# Beechat_Crank_v1_2_B.net
KiCad netlist of a schematic drawn in EAGLE
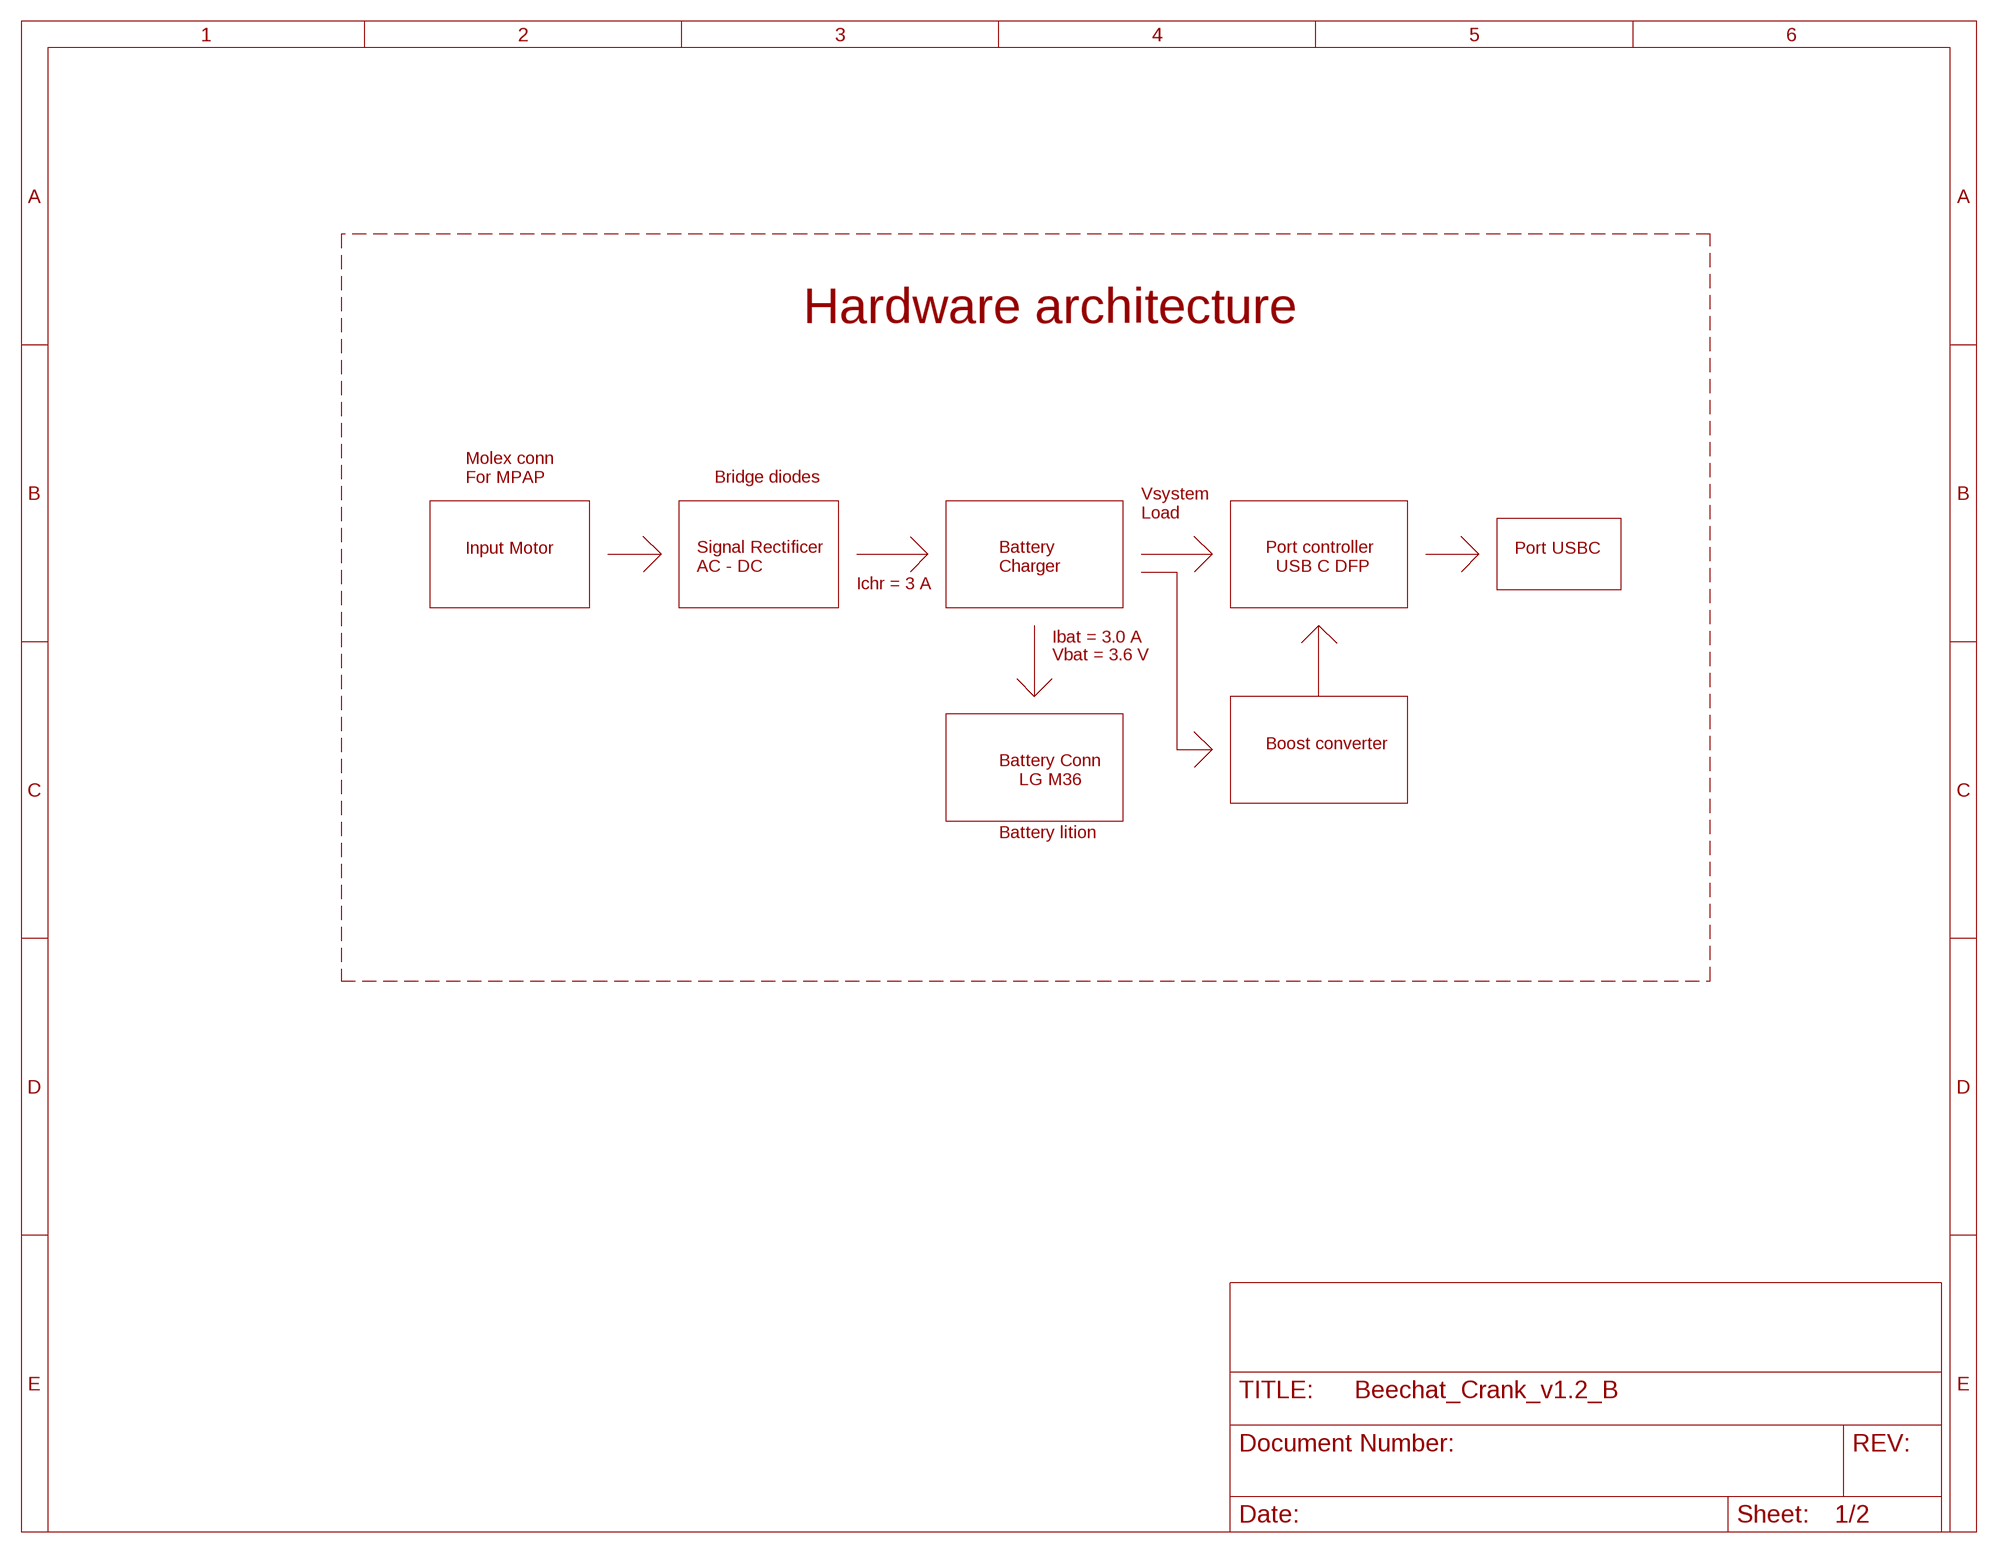
[diagram p0: schematic, sheet 1]
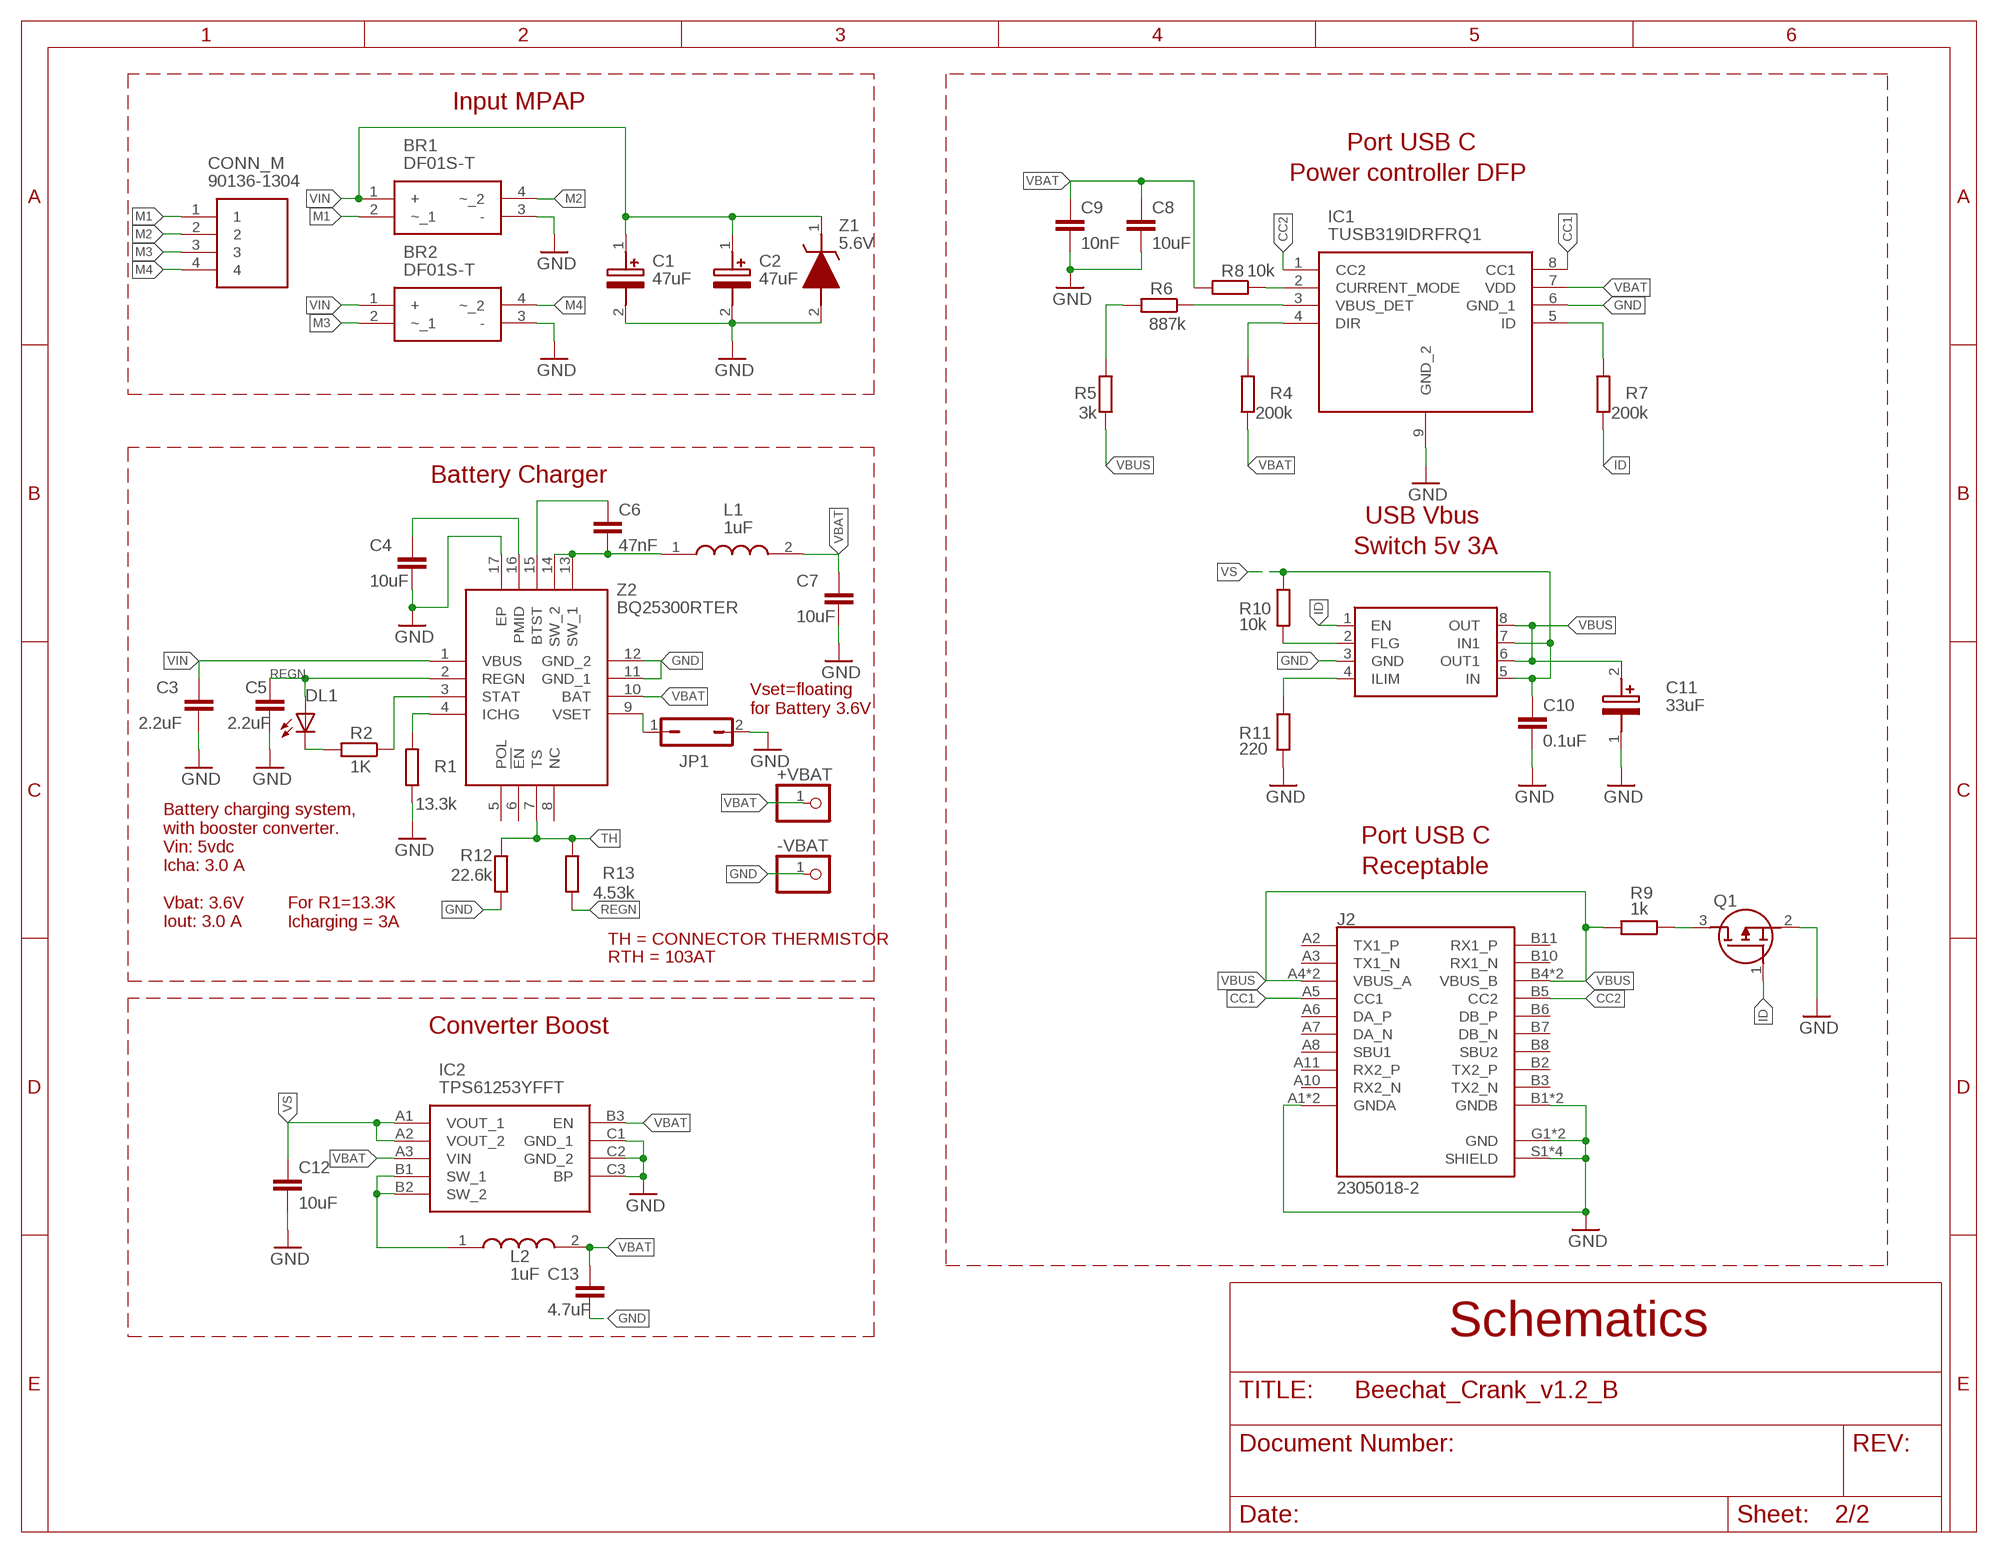
[diagram p1: schematic, sheet 2]

(export (version "E")
  (design (tool "Eeschema 10.0.6"))
  (components
    (comp (ref "+VBAT")
      (value "PINHD-1X1")
      (footprint "eagle-import:1X01")
      (libsource (lib "eagle-import") (part "PINHD-1X1"))
    )
    (comp (ref "-VBAT")
      (value "PINHD-1X1")
      (footprint "eagle-import:1X01")
      (libsource (lib "eagle-import") (part "PINHD-1X1"))
    )
    (comp (ref "BR1")
      (value "DF01S-T")
      (footprint "eagle-import:SOP510P1040X293-4N")
      (fields (field (name "MOUSER_PART_NUMBER") "621-DF01ST"))
      (libsource (lib "eagle-import") (part "DF01S-T"))
    )
    (comp (ref "BR2")
      (value "DF01S-T")
      (footprint "eagle-import:SOP510P1040X293-4N")
      (fields (field (name "MOUSER_PART_NUMBER") "621-DF01ST"))
      (libsource (lib "eagle-import") (part "DF01S-T"))
    )
    (comp (ref "C1")
      (value "47uF")
      (footprint "eagle-import:CAPAE660X800N")
      (fields
        (field (name "MANUFACTURER_PART_NUMBER") "EEE-HDV470XAP")
        (field (name "MOUSER_PART_NUMBER") "667-EEE-HDV470XAP")
      )
      (libsource (lib "eagle-import") (part "EEE-HDV470XAP"))
    )
    (comp (ref "C2")
      (value "47uF")
      (footprint "eagle-import:CAPAE660X800N")
      (fields
        (field (name "MANUFACTURER_PART_NUMBER") "EEE-HDV470XAP")
        (field (name "MOUSER_PART_NUMBER") "667-EEE-HDV470XAP")
      )
      (libsource (lib "eagle-import") (part "EEE-HDV470XAP"))
    )
    (comp (ref "C3")
      (value "2.2uF")
      (footprint "eagle-import:C0603")
      (libsource (lib "eagle-import") (part "C-EUC0603"))
    )
    (comp (ref "C4")
      (value "10uF")
      (footprint "eagle-import:C1210")
      (libsource (lib "eagle-import") (part "C-EUC1210"))
    )
    (comp (ref "C5")
      (value "2.2uF")
      (footprint "eagle-import:C0603")
      (libsource (lib "eagle-import") (part "C-EUC0603"))
    )
    (comp (ref "C6")
      (value "47nF")
      (footprint "eagle-import:C0603")
      (libsource (lib "eagle-import") (part "C-EUC0603"))
    )
    (comp (ref "C7")
      (value "10uF")
      (footprint "eagle-import:C1210")
      (libsource (lib "eagle-import") (part "C-EUC1210"))
    )
    (comp (ref "C8")
      (value "10uF")
      (footprint "eagle-import:C0603")
      (libsource (lib "eagle-import") (part "C-EUC0603"))
    )
    (comp (ref "C9")
      (value "10nF")
      (footprint "eagle-import:C0603")
      (libsource (lib "eagle-import") (part "C-EUC0603"))
    )
    (comp (ref "C10")
      (value "0.1uF")
      (footprint "eagle-import:C0603")
      (libsource (lib "eagle-import") (part "C-EUC0603"))
    )
    (comp (ref "C11")
      (value "33uF")
      (footprint "eagle-import:CAPAE660X550N")
      (fields
        (field (name "MANUFACTURER_PART_NUMBER") "865230343003")
        (field (name "MOUSER_PART_NUMBER") "710-865230343003")
      )
      (libsource (lib "eagle-import") (part "865230343003"))
    )
    (comp (ref "C12")
      (value "10uF")
      (footprint "eagle-import:C0603")
      (libsource (lib "eagle-import") (part "C-EUC0603"))
    )
    (comp (ref "C13")
      (value "4.7uF")
      (footprint "eagle-import:C0603")
      (libsource (lib "eagle-import") (part "C-EUC0603"))
    )
    (comp (ref "CONN_M")
      (value "90136-1304")
      (footprint "eagle-import:SHDR4W65P0X254_1X4_1351X721X11")
      (fields (field (name "MOUSER_PART_NUMBER") "538-90136-1304"))
      (libsource (lib "eagle-import") (part "90136-1304"))
    )
    (comp (ref "DL1")
      (value "LED_BLUE")
      (footprint "eagle-import:CHIP-LED0603")
      (libsource (lib "eagle-import") (part "LEDSMD0603"))
    )
    (comp (ref "IC1")
      (value "TUSB319IDRFRQ1")
      (footprint "eagle-import:SON50P200X200X80-9N")
      (fields (field (name "MOUSER_PART_NUMBER") "595-TUSB319IDRFRQ1"))
      (libsource (lib "eagle-import") (part "TUSB319IDRFRQ1"))
    )
    (comp (ref "IC2")
      (value "TPS61253YFFT")
      (footprint "eagle-import:BGA9C40P3X3_121X131X62")
      (fields (field (name "MOUSER_PART_NUMBER") "595-TPS61253YFFT"))
      (libsource (lib "eagle-import") (part "TPS61253YFFT"))
    )
    (comp (ref "J2")
      (value "2305018-2")
      (footprint "eagle-import:TE_2305018-2")
      (fields (field (name "MF") "TE Connectivity"))
      (libsource (lib "eagle-import") (part "2305018-2"))
    )
    (comp (ref "JP1")
      (value "JP1Q")
      (footprint "eagle-import:JP1")
      (libsource (lib "eagle-import") (part "JP1Q"))
    )
    (comp (ref "L1")
      (value "1uF")
      (footprint "eagle-import:LQH5BPB100MT0L")
      (fields
        (field (name "MANUFACTURER_PART_NUMBER") "LQH5BPB1R0NT0L")
        (field (name "MOUSER_PART_NUMBER") "81-LQH5BPB1R0NT0L")
      )
      (libsource (lib "eagle-import") (part "LQH5BPB1R0NT0L"))
    )
    (comp (ref "L2")
      (value "1uF")
      (footprint "eagle-import:LQH5BPB100MT0L")
      (fields
        (field (name "MANUFACTURER_PART_NUMBER") "LQH5BPB1R0NT0L")
        (field (name "MOUSER_PART_NUMBER") "81-LQH5BPB1R0NT0L")
      )
      (libsource (lib "eagle-import") (part "LQH5BPB1R0NT0L"))
    )
    (comp (ref "Q1")
      (value "SI2337DS-T1-BE3")
      (footprint "eagle-import:SOT95P237X112-3N")
      (fields (field (name "MOUSER_PART_NUMBER") "78-SI2337DS-T1-BE3"))
      (libsource (lib "eagle-import") (part "SI2337DS-T1-BE3"))
    )
    (comp (ref "R1")
      (value "13.3k")
      (footprint "eagle-import:R0603")
      (libsource (lib "eagle-import") (part "R_0603"))
    )
    (comp (ref "R2")
      (value "1K")
      (footprint "eagle-import:R0603")
      (libsource (lib "eagle-import") (part "R_0603"))
    )
    (comp (ref "R4")
      (value "200k")
      (footprint "eagle-import:R0603")
      (libsource (lib "eagle-import") (part "R_0603"))
    )
    (comp (ref "R5")
      (value "3k")
      (footprint "eagle-import:R0603")
      (libsource (lib "eagle-import") (part "R_0603"))
    )
    (comp (ref "R6")
      (value "887k")
      (footprint "eagle-import:R0603")
      (libsource (lib "eagle-import") (part "R_0603"))
    )
    (comp (ref "R7")
      (value "200k")
      (footprint "eagle-import:R0603")
      (libsource (lib "eagle-import") (part "R_0603"))
    )
    (comp (ref "R8")
      (value "10k")
      (footprint "eagle-import:R0603")
      (libsource (lib "eagle-import") (part "R_0603"))
    )
    (comp (ref "R9")
      (value "1k")
      (footprint "eagle-import:R0603")
      (libsource (lib "eagle-import") (part "R_0603"))
    )
    (comp (ref "R10")
      (value "10k")
      (footprint "eagle-import:R0603")
      (libsource (lib "eagle-import") (part "R_0603"))
    )
    (comp (ref "R11")
      (value "220")
      (footprint "eagle-import:R0603")
      (libsource (lib "eagle-import") (part "R_0603"))
    )
    (comp (ref "R12")
      (value "22.6k")
      (footprint "eagle-import:R0603")
      (libsource (lib "eagle-import") (part "R_0603"))
    )
    (comp (ref "R13")
      (value "4.53k")
      (footprint "eagle-import:R0603")
      (libsource (lib "eagle-import") (part "R_0603"))
    )
    (comp (ref "U$1")
      (value "MIC2545")
      (footprint "eagle-import:SOIC127P599X173-8N")
      (libsource (lib "eagle-import") (part "MIC2545"))
    )
    (comp (ref "Z1")
      (value "5.6V")
      (footprint "eagle-import:SOD3716X135N")
      (fields
        (field (name "MANUFACTURER_PART_NUMBER") "MMSZ5V6T3G")
        (field (name "MOUSER_PART_NUMBER") "863-MMSZ5V6T3G")
      )
      (libsource (lib "eagle-import") (part "MMSZ5V6T3G"))
    )
    (comp (ref "Z2")
      (value "BQ25300RTER")
      (footprint "eagle-import:QFN50P300X300X80-17N")
      (fields (field (name "MOUSER_PART_NUMBER") "595-BQ25300RTER"))
      (libsource (lib "eagle-import") (part "BQ25300RTER"))
    )
  )
  (nets
    (net (code "1") (name "CC1") (class "Default")
      (node (ref "IC1") (pin "8") (pinfunction "CC1_8") (pintype "bidirectional"))
      (node (ref "J2") (pin "A5") (pinfunction "CC1_A5") (pintype "passive"))
    )
    (net (code "2") (name "CC2") (class "Default")
      (node (ref "IC1") (pin "1") (pinfunction "CC2_1") (pintype "bidirectional"))
      (node (ref "J2") (pin "B5") (pinfunction "CC2_B5") (pintype "passive"))
    )
    (net (code "3") (name "GND") (class "Default")
      (node (ref "-VBAT") (pin "1") (pinfunction "1_1") (pintype "passive"))
      (node (ref "BR1") (pin "3") (pinfunction "-_3") (pintype "bidirectional"))
      (node (ref "BR2") (pin "3") (pinfunction "-_3") (pintype "bidirectional"))
      (node (ref "C1") (pin "2") (pinfunction "-_2") (pintype "bidirectional"))
      (node (ref "C10") (pin "2") (pinfunction "2_2") (pintype "passive"))
      (node (ref "C11") (pin "1") (pinfunction "-_1") (pintype "bidirectional"))
      (node (ref "C12") (pin "2") (pinfunction "2_2") (pintype "passive"))
      (node (ref "C13") (pin "2") (pinfunction "2_2") (pintype "passive"))
      (node (ref "C2") (pin "2") (pinfunction "-_2") (pintype "bidirectional"))
      (node (ref "C3") (pin "2") (pinfunction "2_2") (pintype "passive"))
      (node (ref "C4") (pin "2") (pinfunction "2_2") (pintype "passive"))
      (node (ref "C5") (pin "2") (pinfunction "2_2") (pintype "passive"))
      (node (ref "C7") (pin "2") (pinfunction "2_2") (pintype "passive"))
      (node (ref "C8") (pin "2") (pinfunction "2_2") (pintype "passive"))
      (node (ref "C9") (pin "2") (pinfunction "2_2") (pintype "passive"))
      (node (ref "IC1") (pin "6") (pinfunction "GND_1_6") (pintype "bidirectional"))
      (node (ref "IC1") (pin "9") (pinfunction "GND_2_9") (pintype "bidirectional"))
      (node (ref "IC2") (pin "C1") (pinfunction "GND_1_C1") (pintype "bidirectional"))
      (node (ref "IC2") (pin "C2") (pinfunction "GND_2_C2") (pintype "bidirectional"))
      (node (ref "IC2") (pin "C3") (pinfunction "BP_C3") (pintype "bidirectional"))
      (node (ref "J2") (pin "A1") (pinfunction "GNDA_A1") (pintype "passive"))
      (node (ref "J2") (pin "A12") (pinfunction "GNDA_A12") (pintype "passive"))
      (node (ref "J2") (pin "B1") (pinfunction "GNDB_B1") (pintype "passive"))
      (node (ref "J2") (pin "B12") (pinfunction "GNDB_B12") (pintype "passive"))
      (node (ref "J2") (pin "G1") (pinfunction "GND_G1") (pintype "power_in"))
      (node (ref "J2") (pin "G2") (pinfunction "GND_G2") (pintype "power_in"))
      (node (ref "J2") (pin "S1") (pinfunction "SHIELD_S1") (pintype "power_in"))
      (node (ref "J2") (pin "S2") (pinfunction "SHIELD_S2") (pintype "power_in"))
      (node (ref "J2") (pin "S3") (pinfunction "SHIELD_S3") (pintype "power_in"))
      (node (ref "J2") (pin "S4") (pinfunction "SHIELD_S4") (pintype "power_in"))
      (node (ref "JP1") (pin "2") (pinfunction "2_2") (pintype "passive"))
      (node (ref "Q1") (pin "2") (pinfunction "S_2") (pintype "bidirectional"))
      (node (ref "R1") (pin "1") (pinfunction "1_1") (pintype "passive"))
      (node (ref "R11") (pin "2") (pinfunction "2_2") (pintype "passive"))
      (node (ref "R12") (pin "1") (pinfunction "1_1") (pintype "passive"))
      (node (ref "U$1") (pin "3") (pinfunction "GND_3") (pintype "bidirectional"))
      (node (ref "Z1") (pin "2") (pinfunction "A_2") (pintype "bidirectional"))
      (node (ref "Z2") (pin "11") (pinfunction "GND_1_11") (pintype "bidirectional"))
      (node (ref "Z2") (pin "12") (pinfunction "GND_2_12") (pintype "bidirectional"))
      (node (ref "Z2") (pin "17") (pinfunction "EP_17") (pintype "bidirectional"))
    )
    (net (code "4") (name "ID") (class "Default")
      (node (ref "Q1") (pin "1") (pinfunction "G_1") (pintype "bidirectional"))
      (node (ref "R7") (pin "1") (pinfunction "1_1") (pintype "passive"))
      (node (ref "U$1") (pin "1") (pinfunction "EN_1") (pintype "bidirectional"))
    )
    (net (code "5") (name "M1") (class "Default")
      (node (ref "BR1") (pin "2") (pinfunction "~{_1}_2") (pintype "bidirectional"))
      (node (ref "CONN_M") (pin "1") (pinfunction "1_1") (pintype "bidirectional"))
    )
    (net (code "6") (name "M2") (class "Default")
      (node (ref "BR1") (pin "4") (pinfunction "~{_2}_4") (pintype "bidirectional"))
      (node (ref "CONN_M") (pin "2") (pinfunction "2_2") (pintype "bidirectional"))
    )
    (net (code "7") (name "M3") (class "Default")
      (node (ref "BR2") (pin "2") (pinfunction "~{_1}_2") (pintype "bidirectional"))
      (node (ref "CONN_M") (pin "3") (pinfunction "3_3") (pintype "bidirectional"))
    )
    (net (code "8") (name "M4") (class "Default")
      (node (ref "BR2") (pin "4") (pinfunction "~{_2}_4") (pintype "bidirectional"))
      (node (ref "CONN_M") (pin "4") (pinfunction "4_4") (pintype "bidirectional"))
    )
    (net (code "9") (name "Net-(DL1-PadC)") (class "Default")
      (node (ref "DL1") (pin "C") (pinfunction "C_C") (pintype "passive"))
      (node (ref "R2") (pin "2") (pinfunction "2_2") (pintype "passive"))
    )
    (net (code "10") (name "Net-(IC1-CURRENT_MODE)") (class "Default")
      (node (ref "IC1") (pin "2") (pinfunction "CURRENT_MODE_2") (pintype "bidirectional"))
      (node (ref "R8") (pin "1") (pinfunction "1_1") (pintype "passive"))
    )
    (net (code "11") (name "Net-(IC1-DIR)") (class "Default")
      (node (ref "IC1") (pin "4") (pinfunction "DIR_4") (pintype "bidirectional"))
      (node (ref "R4") (pin "2") (pinfunction "2_2") (pintype "passive"))
    )
    (net (code "12") (name "Net-(IC1-ID)") (class "Default")
      (node (ref "IC1") (pin "5") (pinfunction "ID_5") (pintype "bidirectional"))
      (node (ref "R7") (pin "2") (pinfunction "2_2") (pintype "passive"))
    )
    (net (code "13") (name "Net-(IC1-VBUS_DET)") (class "Default")
      (node (ref "IC1") (pin "3") (pinfunction "VBUS_DET_3") (pintype "bidirectional"))
      (node (ref "R6") (pin "1") (pinfunction "1_1") (pintype "passive"))
    )
    (net (code "14") (name "Net-(IC2-SW_1)") (class "Default")
      (node (ref "IC2") (pin "B1") (pinfunction "SW_1_B1") (pintype "bidirectional"))
      (node (ref "IC2") (pin "B2") (pinfunction "SW_2_B2") (pintype "bidirectional"))
      (node (ref "L2") (pin "1") (pinfunction "1_1") (pintype "bidirectional"))
    )
    (net (code "15") (name "Net-(Q1-D)") (class "Default")
      (node (ref "Q1") (pin "3") (pinfunction "D_3") (pintype "bidirectional"))
      (node (ref "R9") (pin "1") (pinfunction "1_1") (pintype "passive"))
    )
    (net (code "16") (name "Net-(R5-Pad2)") (class "Default")
      (node (ref "R5") (pin "2") (pinfunction "2_2") (pintype "passive"))
      (node (ref "R6") (pin "2") (pinfunction "2_2") (pintype "passive"))
    )
    (net (code "17") (name "Net-(U$1-FLG)") (class "Default")
      (node (ref "R10") (pin "2") (pinfunction "2_2") (pintype "passive"))
      (node (ref "U$1") (pin "2") (pinfunction "FLG_2") (pintype "bidirectional"))
    )
    (net (code "18") (name "Net-(U$1-ILIM)") (class "Default")
      (node (ref "R11") (pin "1") (pinfunction "1_1") (pintype "passive"))
      (node (ref "U$1") (pin "4") (pinfunction "ILIM_4") (pintype "bidirectional"))
    )
    (net (code "19") (name "Net-(Z2-BTST)") (class "Default")
      (node (ref "C6") (pin "1") (pinfunction "1_1") (pintype "passive"))
      (node (ref "Z2") (pin "15") (pinfunction "BTST_15") (pintype "bidirectional"))
    )
    (net (code "20") (name "Net-(Z2-ICHG)") (class "Default")
      (node (ref "R1") (pin "2") (pinfunction "2_2") (pintype "passive"))
      (node (ref "Z2") (pin "4") (pinfunction "ICHG_4") (pintype "bidirectional"))
    )
    (net (code "21") (name "Net-(Z2-PMID)") (class "Default")
      (node (ref "C4") (pin "1") (pinfunction "1_1") (pintype "passive"))
      (node (ref "Z2") (pin "16") (pinfunction "PMID_16") (pintype "bidirectional"))
    )
    (net (code "22") (name "Net-(Z2-STAT)") (class "Default")
      (node (ref "R2") (pin "1") (pinfunction "1_1") (pintype "passive"))
      (node (ref "Z2") (pin "3") (pinfunction "STAT_3") (pintype "bidirectional"))
    )
    (net (code "23") (name "Net-(Z2-SW_1)") (class "Default")
      (node (ref "C6") (pin "2") (pinfunction "2_2") (pintype "passive"))
      (node (ref "L1") (pin "1") (pinfunction "1_1") (pintype "bidirectional"))
      (node (ref "Z2") (pin "13") (pinfunction "SW_1_13") (pintype "bidirectional"))
      (node (ref "Z2") (pin "14") (pinfunction "SW_2_14") (pintype "bidirectional"))
    )
    (net (code "24") (name "Net-(Z2-VSET)") (class "Default")
      (node (ref "JP1") (pin "1") (pinfunction "1_1") (pintype "passive"))
      (node (ref "Z2") (pin "9") (pinfunction "VSET_9") (pintype "bidirectional"))
    )
    (net (code "25") (name "REGN") (class "Default")
      (node (ref "C5") (pin "1") (pinfunction "1_1") (pintype "passive"))
      (node (ref "DL1") (pin "A") (pinfunction "A_A") (pintype "passive"))
      (node (ref "R13") (pin "1") (pinfunction "1_1") (pintype "passive"))
      (node (ref "Z2") (pin "2") (pinfunction "REGN_2") (pintype "bidirectional"))
    )
    (net (code "26") (name "TH") (class "Default")
      (node (ref "R12") (pin "2") (pinfunction "2_2") (pintype "passive"))
      (node (ref "R13") (pin "2") (pinfunction "2_2") (pintype "passive"))
      (node (ref "Z2") (pin "7") (pinfunction "TS_7") (pintype "bidirectional"))
    )
    (net (code "27") (name "VBAT") (class "Default")
      (node (ref "+VBAT") (pin "1") (pinfunction "1_1") (pintype "passive"))
      (node (ref "C13") (pin "1") (pinfunction "1_1") (pintype "passive"))
      (node (ref "C7") (pin "1") (pinfunction "1_1") (pintype "passive"))
      (node (ref "C8") (pin "1") (pinfunction "1_1") (pintype "passive"))
      (node (ref "C9") (pin "1") (pinfunction "1_1") (pintype "passive"))
      (node (ref "IC1") (pin "7") (pinfunction "VDD_7") (pintype "bidirectional"))
      (node (ref "IC2") (pin "A3") (pinfunction "VIN_A3") (pintype "bidirectional"))
      (node (ref "IC2") (pin "B3") (pinfunction "EN_B3") (pintype "bidirectional"))
      (node (ref "L1") (pin "2") (pinfunction "2_2") (pintype "bidirectional"))
      (node (ref "L2") (pin "2") (pinfunction "2_2") (pintype "bidirectional"))
      (node (ref "R4") (pin "1") (pinfunction "1_1") (pintype "passive"))
      (node (ref "R8") (pin "2") (pinfunction "2_2") (pintype "passive"))
      (node (ref "Z2") (pin "10") (pinfunction "BAT_10") (pintype "bidirectional"))
    )
    (net (code "28") (name "VBUS") (class "Default")
      (node (ref "C11") (pin "2") (pinfunction "+_2") (pintype "bidirectional"))
      (node (ref "J2") (pin "A4") (pinfunction "VBUS_A_A4") (pintype "passive"))
      (node (ref "J2") (pin "A9") (pinfunction "VBUS_A_A9") (pintype "passive"))
      (node (ref "J2") (pin "B4") (pinfunction "VBUS_B_B4") (pintype "passive"))
      (node (ref "J2") (pin "B9") (pinfunction "VBUS_B_B9") (pintype "passive"))
      (node (ref "R5") (pin "1") (pinfunction "1_1") (pintype "passive"))
      (node (ref "R9") (pin "2") (pinfunction "2_2") (pintype "passive"))
      (node (ref "U$1") (pin "6") (pinfunction "OUT1_6") (pintype "bidirectional"))
      (node (ref "U$1") (pin "8") (pinfunction "OUT_8") (pintype "bidirectional"))
    )
    (net (code "29") (name "VIN") (class "Default")
      (node (ref "BR1") (pin "1") (pinfunction "+_1") (pintype "bidirectional"))
      (node (ref "BR2") (pin "1") (pinfunction "+_1") (pintype "bidirectional"))
      (node (ref "C1") (pin "1") (pinfunction "+_1") (pintype "bidirectional"))
      (node (ref "C2") (pin "1") (pinfunction "+_1") (pintype "bidirectional"))
      (node (ref "C3") (pin "1") (pinfunction "1_1") (pintype "passive"))
      (node (ref "Z1") (pin "1") (pinfunction "K_1") (pintype "bidirectional"))
      (node (ref "Z2") (pin "1") (pinfunction "VBUS_1") (pintype "bidirectional"))
    )
    (net (code "30") (name "VS") (class "Default")
      (node (ref "C10") (pin "1") (pinfunction "1_1") (pintype "passive"))
      (node (ref "C12") (pin "1") (pinfunction "1_1") (pintype "passive"))
      (node (ref "IC2") (pin "A1") (pinfunction "VOUT_1_A1") (pintype "bidirectional"))
      (node (ref "IC2") (pin "A2") (pinfunction "VOUT_2_A2") (pintype "bidirectional"))
      (node (ref "R10") (pin "1") (pinfunction "1_1") (pintype "passive"))
      (node (ref "U$1") (pin "5") (pinfunction "IN_5") (pintype "bidirectional"))
      (node (ref "U$1") (pin "7") (pinfunction "IN1_7") (pintype "bidirectional"))
    )
    (net (code "31") (name "unconnected-(J2-DA_N-PadA7)") (class "Default")
      (node (ref "J2") (pin "A7") (pinfunction "DA_N_A7") (pintype "passive"))
    )
    (net (code "32") (name "unconnected-(J2-DA_P-PadA6)") (class "Default")
      (node (ref "J2") (pin "A6") (pinfunction "DA_P_A6") (pintype "passive"))
    )
    (net (code "33") (name "unconnected-(J2-DB_N-PadB7)") (class "Default")
      (node (ref "J2") (pin "B7") (pinfunction "DB_N_B7") (pintype "passive"))
    )
    (net (code "34") (name "unconnected-(J2-DB_P-PadB6)") (class "Default")
      (node (ref "J2") (pin "B6") (pinfunction "DB_P_B6") (pintype "passive"))
    )
    (net (code "35") (name "unconnected-(J2-RX1_N-PadB10)") (class "Default")
      (node (ref "J2") (pin "B10") (pinfunction "RX1_N_B10") (pintype "passive"))
    )
    (net (code "36") (name "unconnected-(J2-RX1_P-PadB11)") (class "Default")
      (node (ref "J2") (pin "B11") (pinfunction "RX1_P_B11") (pintype "passive"))
    )
    (net (code "37") (name "unconnected-(J2-RX2_N-PadA10)") (class "Default")
      (node (ref "J2") (pin "A10") (pinfunction "RX2_N_A10") (pintype "passive"))
    )
    (net (code "38") (name "unconnected-(J2-RX2_P-PadA11)") (class "Default")
      (node (ref "J2") (pin "A11") (pinfunction "RX2_P_A11") (pintype "passive"))
    )
    (net (code "39") (name "unconnected-(J2-SBU1-PadA8)") (class "Default")
      (node (ref "J2") (pin "A8") (pinfunction "SBU1_A8") (pintype "passive"))
    )
    (net (code "40") (name "unconnected-(J2-SBU2-PadB8)") (class "Default")
      (node (ref "J2") (pin "B8") (pinfunction "SBU2_B8") (pintype "passive"))
    )
    (net (code "41") (name "unconnected-(J2-TX1_N-PadA3)") (class "Default")
      (node (ref "J2") (pin "A3") (pinfunction "TX1_N_A3") (pintype "passive"))
    )
    (net (code "42") (name "unconnected-(J2-TX1_P-PadA2)") (class "Default")
      (node (ref "J2") (pin "A2") (pinfunction "TX1_P_A2") (pintype "passive"))
    )
    (net (code "43") (name "unconnected-(J2-TX2_N-PadB3)") (class "Default")
      (node (ref "J2") (pin "B3") (pinfunction "TX2_N_B3") (pintype "passive"))
    )
    (net (code "44") (name "unconnected-(J2-TX2_P-PadB2)") (class "Default")
      (node (ref "J2") (pin "B2") (pinfunction "TX2_P_B2") (pintype "passive"))
    )
    (net (code "45") (name "unconnected-(Z2-NC-Pad8)") (class "Default")
      (node (ref "Z2") (pin "8") (pinfunction "NC_8") (pintype "no_connect"))
    )
    (net (code "46") (name "unconnected-(Z2-POL-Pad5)") (class "Default")
      (node (ref "Z2") (pin "5") (pinfunction "POL_5") (pintype "bidirectional"))
    )
    (net (code "47") (name "unconnected-(Z2-~{EN}-Pad6)") (class "Default")
      (node (ref "Z2") (pin "6") (pinfunction "~{EN}_6") (pintype "bidirectional"))
    )
  )
)
